# rp2040_core.net
KiCad netlist of a schematic drawn in Altium Designer
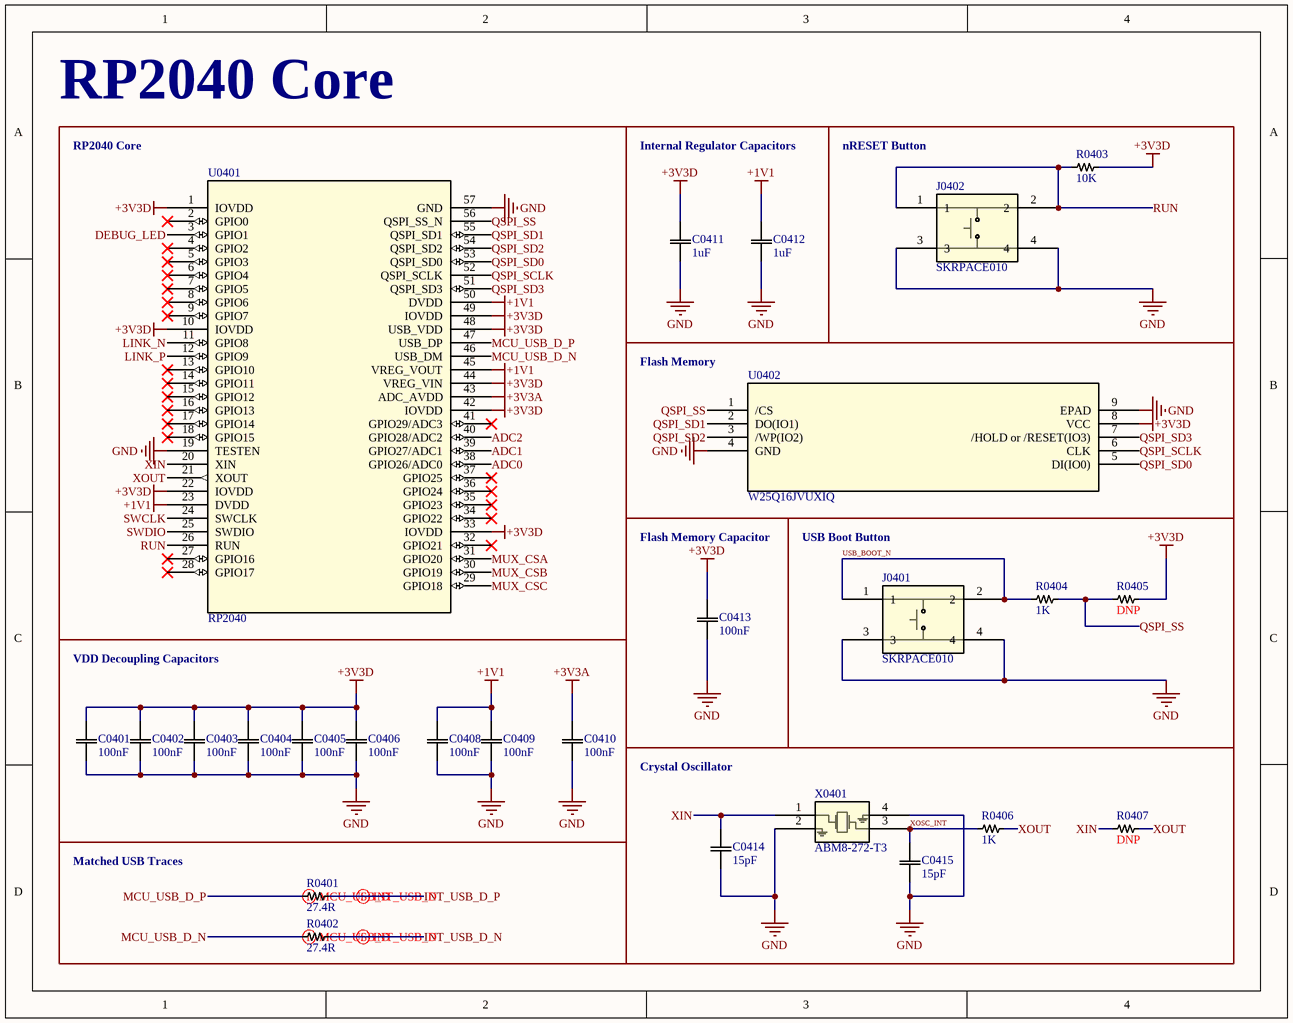
[diagram p0: rp2040_core.SchDoc]

(export (version "E")
  (design (tool "Eeschema 10.0.6"))
  (components
    (comp (ref "C0401")
      (value "100nF")
      (footprint "CAPC10555_55N_KEM")
      (description "SMD Comm X7R, Ceramic, SMD, MLCC, Temperature Stable, 0402")
      (fields
        (field (name "MANUFACTURER_PART_NUMBER") "C0402C104K4RACTU")
        (field (name "COPYRIGHT") "Copyright (C) 2025 Ultra Librarian. All rights reserved.")
      )
      (libsource (lib "SplitHE_Int") (part "C0402"))
    )
    (comp (ref "C0402")
      (value "100nF")
      (footprint "CAPC10555_55N_KEM")
      (description "SMD Comm X7R, Ceramic, SMD, MLCC, Temperature Stable, 0402")
      (fields
        (field (name "MANUFACTURER_PART_NUMBER") "C0402C104K4RACTU")
        (field (name "COPYRIGHT") "Copyright (C) 2025 Ultra Librarian. All rights reserved.")
      )
      (libsource (lib "SplitHE_Int") (part "C0402"))
    )
    (comp (ref "C0403")
      (value "100nF")
      (footprint "CAPC10555_55N_KEM")
      (description "SMD Comm X7R, Ceramic, SMD, MLCC, Temperature Stable, 0402")
      (fields
        (field (name "MANUFACTURER_PART_NUMBER") "C0402C104K4RACTU")
        (field (name "COPYRIGHT") "Copyright (C) 2025 Ultra Librarian. All rights reserved.")
      )
      (libsource (lib "SplitHE_Int") (part "C0402"))
    )
    (comp (ref "C0404")
      (value "100nF")
      (footprint "CAPC10555_55N_KEM")
      (description "SMD Comm X7R, Ceramic, SMD, MLCC, Temperature Stable, 0402")
      (fields
        (field (name "MANUFACTURER_PART_NUMBER") "C0402C104K4RACTU")
        (field (name "COPYRIGHT") "Copyright (C) 2025 Ultra Librarian. All rights reserved.")
      )
      (libsource (lib "SplitHE_Int") (part "C0402"))
    )
    (comp (ref "C0405")
      (value "100nF")
      (footprint "CAPC10555_55N_KEM")
      (description "SMD Comm X7R, Ceramic, SMD, MLCC, Temperature Stable, 0402")
      (fields
        (field (name "MANUFACTURER_PART_NUMBER") "C0402C104K4RACTU")
        (field (name "COPYRIGHT") "Copyright (C) 2025 Ultra Librarian. All rights reserved.")
      )
      (libsource (lib "SplitHE_Int") (part "C0402"))
    )
    (comp (ref "C0406")
      (value "100nF")
      (footprint "CAPC10555_55N_KEM")
      (description "SMD Comm X7R, Ceramic, SMD, MLCC, Temperature Stable, 0402")
      (fields
        (field (name "MANUFACTURER_PART_NUMBER") "C0402C104K4RACTU")
        (field (name "COPYRIGHT") "Copyright (C) 2025 Ultra Librarian. All rights reserved.")
      )
      (libsource (lib "SplitHE_Int") (part "C0402"))
    )
    (comp (ref "C0408")
      (value "100nF")
      (footprint "CAPC10555_55N_KEM")
      (description "SMD Comm X7R, Ceramic, SMD, MLCC, Temperature Stable, 0402")
      (fields
        (field (name "MANUFACTURER_PART_NUMBER") "C0402C104K4RACTU")
        (field (name "COPYRIGHT") "Copyright (C) 2025 Ultra Librarian. All rights reserved.")
      )
      (libsource (lib "SplitHE_Int") (part "C0402"))
    )
    (comp (ref "C0409")
      (value "100nF")
      (footprint "CAPC10555_55N_KEM")
      (description "SMD Comm X7R, Ceramic, SMD, MLCC, Temperature Stable, 0402")
      (fields
        (field (name "MANUFACTURER_PART_NUMBER") "C0402C104K4RACTU")
        (field (name "COPYRIGHT") "Copyright (C) 2025 Ultra Librarian. All rights reserved.")
      )
      (libsource (lib "SplitHE_Int") (part "C0402"))
    )
    (comp (ref "C0410")
      (value "100nF")
      (footprint "CAPC10555_55N_KEM")
      (description "SMD Comm X7R, Ceramic, SMD, MLCC, Temperature Stable, 0402")
      (fields
        (field (name "MANUFACTURER_PART_NUMBER") "C0402C104K4RACTU")
        (field (name "COPYRIGHT") "Copyright (C) 2025 Ultra Librarian. All rights reserved.")
      )
      (libsource (lib "SplitHE_Int") (part "C0402"))
    )
    (comp (ref "C0411")
      (value "1uF")
      (footprint "CAPC10555_55N_KEM")
      (description "SMD Comm X7R, Ceramic, SMD, MLCC, Temperature Stable, 0402")
      (fields
        (field (name "MANUFACTURER_PART_NUMBER") "C0402C104K4RACTU")
        (field (name "COPYRIGHT") "Copyright (C) 2025 Ultra Librarian. All rights reserved.")
      )
      (libsource (lib "SplitHE_Int") (part "C0402"))
    )
    (comp (ref "C0412")
      (value "1uF")
      (footprint "CAPC10555_55N_KEM")
      (description "SMD Comm X7R, Ceramic, SMD, MLCC, Temperature Stable, 0402")
      (fields
        (field (name "MANUFACTURER_PART_NUMBER") "C0402C104K4RACTU")
        (field (name "COPYRIGHT") "Copyright (C) 2025 Ultra Librarian. All rights reserved.")
      )
      (libsource (lib "SplitHE_Int") (part "C0402"))
    )
    (comp (ref "C0413")
      (value "100nF")
      (footprint "CAPC10555_55N_KEM")
      (description "SMD Comm X7R, Ceramic, SMD, MLCC, Temperature Stable, 0402")
      (fields
        (field (name "MANUFACTURER_PART_NUMBER") "C0402C104K4RACTU")
        (field (name "COPYRIGHT") "Copyright (C) 2025 Ultra Librarian. All rights reserved.")
      )
      (libsource (lib "SplitHE_Int") (part "C0402"))
    )
    (comp (ref "C0414")
      (value "15pF")
      (footprint "CAPC10555_55N_KEM")
      (description "SMD Comm X7R, Ceramic, SMD, MLCC, Temperature Stable, 0402")
      (fields
        (field (name "MANUFACTURER_PART_NUMBER") "C0402C104K4RACTU")
        (field (name "COPYRIGHT") "Copyright (C) 2025 Ultra Librarian. All rights reserved.")
      )
      (libsource (lib "SplitHE_Int") (part "C0402"))
    )
    (comp (ref "C0415")
      (value "15pF")
      (footprint "CAPC10555_55N_KEM")
      (description "SMD Comm X7R, Ceramic, SMD, MLCC, Temperature Stable, 0402")
      (fields
        (field (name "MANUFACTURER_PART_NUMBER") "C0402C104K4RACTU")
        (field (name "COPYRIGHT") "Copyright (C) 2025 Ultra Librarian. All rights reserved.")
      )
      (libsource (lib "SplitHE_Int") (part "C0402"))
    )
    (comp (ref "J0401")
      (value "SKRPACE010")
      (footprint "SW_SKRPACE010_AAL")
      (description "No Description Available")
      (fields (field (name "COPYRIGHT") "Copyright (C) 2025 Ultra Librarian. All rights reserved."))
      (libsource (lib "SKRPACE010") (part "SKRPACE010"))
    )
    (comp (ref "J0402")
      (value "SKRPACE010")
      (footprint "SW_SKRPACE010_AAL")
      (description "No Description Available")
      (fields (field (name "COPYRIGHT") "Copyright (C) 2025 Ultra Librarian. All rights reserved."))
      (libsource (lib "SKRPACE010") (part "SKRPACE010"))
    )
    (comp (ref "R0401")
      (value "27.4R")
      (footprint "RES0402_CPF_TYCO_TYC")
      (description "CPF 0402 RL")
      (fields
        (field (name "MANUFACTURER_PART_NUMBER") "CPF0402B33RE1")
        (field (name "COPYRIGHT") "Copyright (C) 2025 Ultra Librarian. All rights reserved.")
      )
      (libsource (lib "SplitHE_Int") (part "R0402"))
    )
    (comp (ref "R0402")
      (value "27.4R")
      (footprint "RES0402_CPF_TYCO_TYC")
      (description "CPF 0402 RL")
      (fields
        (field (name "MANUFACTURER_PART_NUMBER") "CPF0402B33RE1")
        (field (name "COPYRIGHT") "Copyright (C) 2025 Ultra Librarian. All rights reserved.")
      )
      (libsource (lib "SplitHE_Int") (part "R0402"))
    )
    (comp (ref "R0403")
      (value "10K")
      (footprint "RC0603N_YAG")
      (description "RES SMD 47K OHM 1% 1/10W 0603")
      (fields
        (field (name "MANUFACTURER_PART_NUMBER") "RC0603FR-0747KL")
        (field (name "COPYRIGHT") "Copyright (C) 2025 Ultra Librarian. All rights reserved.")
      )
      (libsource (lib "SplitHE_Int") (part "RC0603"))
    )
    (comp (ref "R0404")
      (value "1K")
      (footprint "RC0603N_YAG")
      (description "RES SMD 47K OHM 1% 1/10W 0603")
      (fields
        (field (name "MANUFACTURER_PART_NUMBER") "RC0603FR-0747KL")
        (field (name "COPYRIGHT") "Copyright (C) 2025 Ultra Librarian. All rights reserved.")
      )
      (libsource (lib "SplitHE_Int") (part "RC0603"))
    )
    (comp (ref "R0405")
      (value "DNP")
      (footprint "RES0402_CPF_TYCO_TYC")
      (description "CPF 0402 RL")
      (fields
        (field (name "MANUFACTURER_PART_NUMBER") "CPF0402B33RE1")
        (field (name "COPYRIGHT") "Copyright (C) 2025 Ultra Librarian. All rights reserved.")
      )
      (libsource (lib "SplitHE_Int") (part "R0402"))
    )
    (comp (ref "R0406")
      (value "1K")
      (footprint "RES0402_CPF_TYCO_TYC")
      (description "CPF 0402 RL")
      (fields
        (field (name "MANUFACTURER_PART_NUMBER") "CPF0402B33RE1")
        (field (name "COPYRIGHT") "Copyright (C) 2025 Ultra Librarian. All rights reserved.")
      )
      (libsource (lib "SplitHE_Int") (part "R0402"))
    )
    (comp (ref "R0407")
      (value "DNP")
      (footprint "RES0402_CPF_TYCO_TYC")
      (description "CPF 0402 RL")
      (fields
        (field (name "MANUFACTURER_PART_NUMBER") "CPF0402B33RE1")
        (field (name "COPYRIGHT") "Copyright (C) 2025 Ultra Librarian. All rights reserved.")
      )
      (libsource (lib "SplitHE_Int") (part "R0402"))
    )
    (comp (ref "U0401")
      (value "RP2040")
      (footprint "IC57_RP2040")
      (description "No Description Available")
      (fields (field (name "COPYRIGHT") "Copyright (C) 2025 Ultra Librarian. All rights reserved."))
      (libsource (lib "SplitHE_Int") (part "RP2040"))
    )
    (comp (ref "U0402")
      (value "W25Q16JVUXIQ")
      (footprint "W25Q16JVUXIQ_WIN")
      (description "No Description Available")
      (fields (field (name "COPYRIGHT") "Copyright (C) 2025 Ultra Librarian. All rights reserved."))
      (libsource (lib "W25Q16JVUXIQ") (part "W25Q16JVUXIQ"))
    )
    (comp (ref "X0401")
      (value "ABM8-272-T3")
      (footprint "ABM8-272-T3_ABR")
      (description "No Description Available")
      (fields (field (name "COPYRIGHT") "Copyright (C) 2025 Ultra Librarian. All rights reserved."))
      (libsource (lib "ABM8-272-T3") (part "ABM8-272-T3"))
    )
  )
  (nets
    (net (code "1") (name "+1V1") (class "Default")
      (node (ref "C0408") (pin "2") (pinfunction "2_2") (pintype "passive"))
      (node (ref "C0409") (pin "2") (pinfunction "2_2") (pintype "passive"))
      (node (ref "C0412") (pin "2") (pinfunction "2_2") (pintype "passive"))
      (node (ref "U0401") (pin "23") (pinfunction "DVDD_23") (pintype "power_in"))
      (node (ref "U0401") (pin "45") (pinfunction "VREG_VOUT_45") (pintype "power_in"))
      (node (ref "U0401") (pin "50") (pinfunction "DVDD_50") (pintype "power_in"))
    )
    (net (code "2") (name "+3V3A") (class "Default")
      (node (ref "C0410") (pin "2") (pinfunction "2_2") (pintype "passive"))
      (node (ref "U0401") (pin "43") (pinfunction "ADC_AVDD_43") (pintype "power_in"))
    )
    (net (code "3") (name "+3V3D") (class "Default")
      (node (ref "C0401") (pin "2") (pinfunction "2_2") (pintype "passive"))
      (node (ref "C0402") (pin "2") (pinfunction "2_2") (pintype "passive"))
      (node (ref "C0403") (pin "2") (pinfunction "2_2") (pintype "passive"))
      (node (ref "C0404") (pin "2") (pinfunction "2_2") (pintype "passive"))
      (node (ref "C0405") (pin "2") (pinfunction "2_2") (pintype "passive"))
      (node (ref "C0406") (pin "2") (pinfunction "2_2") (pintype "passive"))
      (node (ref "C0411") (pin "2") (pinfunction "2_2") (pintype "passive"))
      (node (ref "C0413") (pin "2") (pinfunction "2_2") (pintype "passive"))
      (node (ref "R0403") (pin "1") (pinfunction "1_1") (pintype "passive"))
      (node (ref "R0405") (pin "1") (pinfunction "1_1") (pintype "passive"))
      (node (ref "U0401") (pin "1") (pinfunction "IOVDD_1") (pintype "power_in"))
      (node (ref "U0401") (pin "10") (pinfunction "IOVDD_10") (pintype "power_in"))
      (node (ref "U0401") (pin "22") (pinfunction "IOVDD_22") (pintype "power_in"))
      (node (ref "U0401") (pin "33") (pinfunction "IOVDD_33") (pintype "power_in"))
      (node (ref "U0401") (pin "42") (pinfunction "IOVDD_42") (pintype "power_in"))
      (node (ref "U0401") (pin "44") (pinfunction "VREG_VIN_44") (pintype "passive"))
      (node (ref "U0401") (pin "48") (pinfunction "USB_VDD_48") (pintype "power_in"))
      (node (ref "U0401") (pin "49") (pinfunction "IOVDD_49") (pintype "power_in"))
      (node (ref "U0402") (pin "8") (pinfunction "VCC_8") (pintype "passive"))
    )
    (net (code "4") (name "/ADC0") (class "Default")
      (node (ref "U0401") (pin "38") (pinfunction "GPIO26/ADC0_38") (pintype "bidirectional"))
    )
    (net (code "5") (name "/ADC1") (class "Default")
      (node (ref "U0401") (pin "39") (pinfunction "GPIO27/ADC1_39") (pintype "bidirectional"))
    )
    (net (code "6") (name "/ADC2") (class "Default")
      (node (ref "U0401") (pin "40") (pinfunction "GPIO28/ADC2_40") (pintype "bidirectional"))
    )
    (net (code "7") (name "/DEBUG_LED") (class "Default")
      (node (ref "U0401") (pin "3") (pinfunction "GPIO1_3") (pintype "bidirectional"))
    )
    (net (code "8") (name "/INT_USB_D_N") (class "Default")
      (node (ref "R0402") (pin "1") (pinfunction "1_1") (pintype "passive"))
    )
    (net (code "9") (name "/INT_USB_D_P") (class "Default")
      (node (ref "R0401") (pin "1") (pinfunction "1_1") (pintype "passive"))
    )
    (net (code "10") (name "/LINK_N") (class "Default")
      (node (ref "U0401") (pin "11") (pinfunction "GPIO8_11") (pintype "bidirectional"))
    )
    (net (code "11") (name "/LINK_P") (class "Default")
      (node (ref "U0401") (pin "12") (pinfunction "GPIO9_12") (pintype "bidirectional"))
    )
    (net (code "12") (name "/MCU_USB_D_N") (class "Default")
      (node (ref "R0402") (pin "2") (pinfunction "2_2") (pintype "passive"))
      (node (ref "U0401") (pin "46") (pinfunction "USB_DM_46") (pintype "passive"))
    )
    (net (code "13") (name "/MCU_USB_D_P") (class "Default")
      (node (ref "R0401") (pin "2") (pinfunction "2_2") (pintype "passive"))
      (node (ref "U0401") (pin "47") (pinfunction "USB_DP_47") (pintype "passive"))
    )
    (net (code "14") (name "/MUX_CSA") (class "Default")
      (node (ref "U0401") (pin "31") (pinfunction "GPIO20_31") (pintype "bidirectional"))
    )
    (net (code "15") (name "/MUX_CSB") (class "Default")
      (node (ref "U0401") (pin "30") (pinfunction "GPIO19_30") (pintype "bidirectional"))
    )
    (net (code "16") (name "/MUX_CSC") (class "Default")
      (node (ref "U0401") (pin "29") (pinfunction "GPIO18_29") (pintype "bidirectional"))
    )
    (net (code "17") (name "/QSPI_SCLK") (class "Default")
      (node (ref "U0401") (pin "52") (pinfunction "QSPI_SCLK_52") (pintype "passive"))
      (node (ref "U0402") (pin "6") (pinfunction "CLK_6") (pintype "passive"))
    )
    (net (code "18") (name "/QSPI_SD0") (class "Default")
      (node (ref "U0401") (pin "53") (pinfunction "QSPI_SD0_53") (pintype "bidirectional"))
      (node (ref "U0402") (pin "5") (pinfunction "DI(IO0)_5") (pintype "passive"))
    )
    (net (code "19") (name "/QSPI_SD1") (class "Default")
      (node (ref "U0401") (pin "55") (pinfunction "QSPI_SD1_55") (pintype "bidirectional"))
      (node (ref "U0402") (pin "2") (pinfunction "DO(IO1)_2") (pintype "passive"))
    )
    (net (code "20") (name "/QSPI_SD2") (class "Default")
      (node (ref "U0401") (pin "54") (pinfunction "QSPI_SD2_54") (pintype "bidirectional"))
      (node (ref "U0402") (pin "3") (pinfunction "/WP(IO2)_3") (pintype "passive"))
    )
    (net (code "21") (name "/QSPI_SD3") (class "Default")
      (node (ref "U0401") (pin "51") (pinfunction "QSPI_SD3_51") (pintype "bidirectional"))
      (node (ref "U0402") (pin "7") (pinfunction "/HOLD_or_/RESET(IO3)_7") (pintype "passive"))
    )
    (net (code "22") (name "/QSPI_SS") (class "Default")
      (node (ref "R0404") (pin "1") (pinfunction "1_1") (pintype "passive"))
      (node (ref "R0405") (pin "2") (pinfunction "2_2") (pintype "passive"))
      (node (ref "U0401") (pin "56") (pinfunction "QSPI_SS_N_56") (pintype "passive"))
      (node (ref "U0402") (pin "1") (pinfunction "/CS_1") (pintype "passive"))
    )
    (net (code "23") (name "/RUN") (class "Default")
      (node (ref "J0402") (pin "1") (pinfunction "1_1") (pintype "passive"))
      (node (ref "J0402") (pin "2") (pinfunction "2_2") (pintype "passive"))
      (node (ref "R0403") (pin "2") (pinfunction "2_2") (pintype "passive"))
      (node (ref "U0401") (pin "26") (pinfunction "RUN_26") (pintype "passive"))
    )
    (net (code "24") (name "/SWCLK") (class "Default")
      (node (ref "U0401") (pin "24") (pinfunction "SWCLK_24") (pintype "passive"))
    )
    (net (code "25") (name "/SWDIO") (class "Default")
      (node (ref "U0401") (pin "25") (pinfunction "SWDIO_25") (pintype "passive"))
    )
    (net (code "26") (name "/USB_BOOT_N") (class "Default")
      (node (ref "J0401") (pin "1") (pinfunction "1_1") (pintype "passive"))
      (node (ref "J0401") (pin "2") (pinfunction "2_2") (pintype "passive"))
      (node (ref "R0404") (pin "2") (pinfunction "2_2") (pintype "passive"))
    )
    (net (code "27") (name "/XIN") (class "Default")
      (node (ref "C0414") (pin "1") (pinfunction "1_1") (pintype "passive"))
      (node (ref "R0407") (pin "1") (pinfunction "1_1") (pintype "passive"))
      (node (ref "U0401") (pin "20") (pinfunction "XIN_20") (pintype "passive"))
      (node (ref "X0401") (pin "1") (pinfunction "1_1") (pintype "passive"))
    )
    (net (code "28") (name "/XOSC_INT") (class "Default")
      (node (ref "C0415") (pin "2") (pinfunction "2_2") (pintype "passive"))
      (node (ref "R0406") (pin "1") (pinfunction "1_1") (pintype "passive"))
      (node (ref "X0401") (pin "3") (pinfunction "3_3") (pintype "passive"))
    )
    (net (code "29") (name "/XOUT") (class "Default")
      (node (ref "R0406") (pin "2") (pinfunction "2_2") (pintype "passive"))
      (node (ref "R0407") (pin "2") (pinfunction "2_2") (pintype "passive"))
      (node (ref "U0401") (pin "21") (pinfunction "XOUT_21") (pintype "output"))
    )
    (net (code "30") (name "GND") (class "Default")
      (node (ref "C0401") (pin "1") (pinfunction "1_1") (pintype "passive"))
      (node (ref "C0402") (pin "1") (pinfunction "1_1") (pintype "passive"))
      (node (ref "C0403") (pin "1") (pinfunction "1_1") (pintype "passive"))
      (node (ref "C0404") (pin "1") (pinfunction "1_1") (pintype "passive"))
      (node (ref "C0405") (pin "1") (pinfunction "1_1") (pintype "passive"))
      (node (ref "C0406") (pin "1") (pinfunction "1_1") (pintype "passive"))
      (node (ref "C0408") (pin "1") (pinfunction "1_1") (pintype "passive"))
      (node (ref "C0409") (pin "1") (pinfunction "1_1") (pintype "passive"))
      (node (ref "C0410") (pin "1") (pinfunction "1_1") (pintype "passive"))
      (node (ref "C0411") (pin "1") (pinfunction "1_1") (pintype "passive"))
      (node (ref "C0412") (pin "1") (pinfunction "1_1") (pintype "passive"))
      (node (ref "C0413") (pin "1") (pinfunction "1_1") (pintype "passive"))
      (node (ref "C0414") (pin "2") (pinfunction "2_2") (pintype "passive"))
      (node (ref "C0415") (pin "1") (pinfunction "1_1") (pintype "passive"))
      (node (ref "J0401") (pin "3") (pinfunction "3_3") (pintype "passive"))
      (node (ref "J0401") (pin "4") (pinfunction "4_4") (pintype "passive"))
      (node (ref "J0402") (pin "3") (pinfunction "3_3") (pintype "passive"))
      (node (ref "J0402") (pin "4") (pinfunction "4_4") (pintype "passive"))
      (node (ref "U0401") (pin "19") (pinfunction "TESTEN_19") (pintype "passive"))
      (node (ref "U0401") (pin "57") (pinfunction "GND_57") (pintype "power_in"))
      (node (ref "U0402") (pin "4") (pinfunction "GND_4") (pintype "passive"))
      (node (ref "U0402") (pin "9") (pinfunction "EPAD_9") (pintype "passive"))
      (node (ref "X0401") (pin "2") (pinfunction "2_2") (pintype "passive"))
      (node (ref "X0401") (pin "4") (pinfunction "4_4") (pintype "passive"))
    )
    (net (code "31") (name "unconnected-(U0401-GPIO0-Pad2)") (class "Default")
      (node (ref "U0401") (pin "2") (pinfunction "GPIO0_2") (pintype "bidirectional+no_connect"))
    )
    (net (code "32") (name "unconnected-(U0401-GPIO2-Pad4)") (class "Default")
      (node (ref "U0401") (pin "4") (pinfunction "GPIO2_4") (pintype "bidirectional+no_connect"))
    )
    (net (code "33") (name "unconnected-(U0401-GPIO3-Pad5)") (class "Default")
      (node (ref "U0401") (pin "5") (pinfunction "GPIO3_5") (pintype "bidirectional+no_connect"))
    )
    (net (code "34") (name "unconnected-(U0401-GPIO4-Pad6)") (class "Default")
      (node (ref "U0401") (pin "6") (pinfunction "GPIO4_6") (pintype "bidirectional+no_connect"))
    )
    (net (code "35") (name "unconnected-(U0401-GPIO5-Pad7)") (class "Default")
      (node (ref "U0401") (pin "7") (pinfunction "GPIO5_7") (pintype "bidirectional+no_connect"))
    )
    (net (code "36") (name "unconnected-(U0401-GPIO6-Pad8)") (class "Default")
      (node (ref "U0401") (pin "8") (pinfunction "GPIO6_8") (pintype "bidirectional+no_connect"))
    )
    (net (code "37") (name "unconnected-(U0401-GPIO7-Pad9)") (class "Default")
      (node (ref "U0401") (pin "9") (pinfunction "GPIO7_9") (pintype "bidirectional+no_connect"))
    )
    (net (code "38") (name "unconnected-(U0401-GPIO10-Pad13)") (class "Default")
      (node (ref "U0401") (pin "13") (pinfunction "GPIO10_13") (pintype "bidirectional+no_connect"))
    )
    (net (code "39") (name "unconnected-(U0401-GPIO11-Pad14)") (class "Default")
      (node (ref "U0401") (pin "14") (pinfunction "GPIO11_14") (pintype "bidirectional+no_connect"))
    )
    (net (code "40") (name "unconnected-(U0401-GPIO12-Pad15)") (class "Default")
      (node (ref "U0401") (pin "15") (pinfunction "GPIO12_15") (pintype "bidirectional+no_connect"))
    )
    (net (code "41") (name "unconnected-(U0401-GPIO13-Pad16)") (class "Default")
      (node (ref "U0401") (pin "16") (pinfunction "GPIO13_16") (pintype "bidirectional+no_connect"))
    )
    (net (code "42") (name "unconnected-(U0401-GPIO14-Pad17)") (class "Default")
      (node (ref "U0401") (pin "17") (pinfunction "GPIO14_17") (pintype "bidirectional+no_connect"))
    )
    (net (code "43") (name "unconnected-(U0401-GPIO15-Pad18)") (class "Default")
      (node (ref "U0401") (pin "18") (pinfunction "GPIO15_18") (pintype "bidirectional+no_connect"))
    )
    (net (code "44") (name "unconnected-(U0401-GPIO16-Pad27)") (class "Default")
      (node (ref "U0401") (pin "27") (pinfunction "GPIO16_27") (pintype "bidirectional+no_connect"))
    )
    (net (code "45") (name "unconnected-(U0401-GPIO17-Pad28)") (class "Default")
      (node (ref "U0401") (pin "28") (pinfunction "GPIO17_28") (pintype "bidirectional+no_connect"))
    )
    (net (code "46") (name "unconnected-(U0401-GPIO21-Pad32)") (class "Default")
      (node (ref "U0401") (pin "32") (pinfunction "GPIO21_32") (pintype "bidirectional+no_connect"))
    )
    (net (code "47") (name "unconnected-(U0401-GPIO22-Pad34)") (class "Default")
      (node (ref "U0401") (pin "34") (pinfunction "GPIO22_34") (pintype "bidirectional+no_connect"))
    )
    (net (code "48") (name "unconnected-(U0401-GPIO23-Pad35)") (class "Default")
      (node (ref "U0401") (pin "35") (pinfunction "GPIO23_35") (pintype "bidirectional+no_connect"))
    )
    (net (code "49") (name "unconnected-(U0401-GPIO24-Pad36)") (class "Default")
      (node (ref "U0401") (pin "36") (pinfunction "GPIO24_36") (pintype "bidirectional+no_connect"))
    )
    (net (code "50") (name "unconnected-(U0401-GPIO25-Pad37)") (class "Default")
      (node (ref "U0401") (pin "37") (pinfunction "GPIO25_37") (pintype "bidirectional+no_connect"))
    )
    (net (code "51") (name "unconnected-(U0401-GPIO29{slash}ADC3-Pad41)") (class "Default")
      (node (ref "U0401") (pin "41") (pinfunction "GPIO29/ADC3_41") (pintype "bidirectional+no_connect"))
    )
  )
)
